# Sheet6.net
KiCad netlist of a schematic drawn in Altium Designer
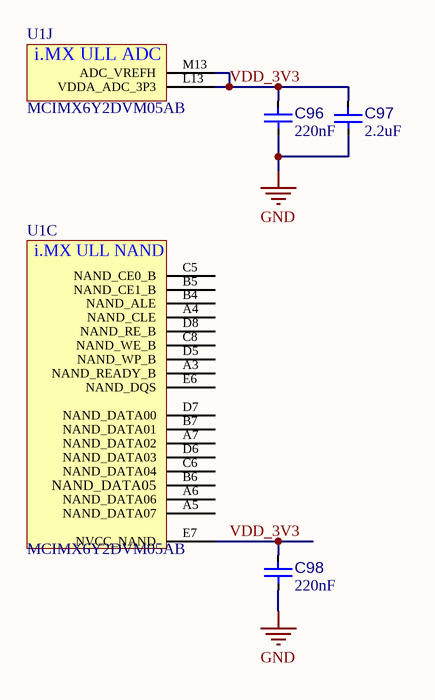
[diagram p0: Sheet6.SchDoc]

(export (version "E")
  (design (tool "Eeschema 10.0.6"))
  (components
    (comp (ref "C96")
      (value "220nF")
      (footprint "0402-SMD-CAP")
      (fields
        (field (name "TOLERANCE") "10%")
        (field (name "VOLTAGE") "16V")
        (field (name "Comment") "GRM155R71C224KA12D")
      )
      (libsource (lib "Budapest University of Technology and Economics") (part "CAP-NP-2"))
    )
    (comp (ref "C97")
      (value "2.2uF")
      (footprint "0603-SMD-CAP")
      (description "CAP CER 2.2UF 10V X7R 0603")
      (fields (field (name "VOLTAGE") "10V") (field (name "TOLERANCE") "10%"))
      (libsource (lib "Budapest University of Technology and Economics") (part "CAP-NP-2"))
    )
    (comp (ref "C98")
      (value "220nF")
      (footprint "0402-SMD-CAP")
      (fields
        (field (name "TOLERANCE") "10%")
        (field (name "VOLTAGE") "16V")
        (field (name "Comment") "GRM155R71C224KA12D")
      )
      (libsource (lib "Budapest University of Technology and Economics") (part "CAP-NP-2"))
    )
    (comp (ref "U1")
      (value "MCIMX6Y2DVM05AB")
      (footprint "BGA100P9X9-81A")
      (libsource (lib "Budapest University of Technology and Economics") (part "MCIMX6Y2DVM05AB"))
    )
  )
  (nets
    (net (code "1") (name "/VDD_3V3") (class "Default")
      (node (ref "C96") (pin "1") (pinfunction "1_1") (pintype "passive"))
      (node (ref "C97") (pin "2") (pinfunction "2_2") (pintype "passive"))
      (node (ref "C98") (pin "1") (pinfunction "1_1") (pintype "passive"))
      (node (ref "U1") (pin "E7") (pinfunction "NVCC_NAND_E7") (pintype "passive"))
      (node (ref "U1") (pin "L13") (pinfunction "VDDA_ADC_3P3_L13") (pintype "passive"))
      (node (ref "U1") (pin "M13") (pinfunction "ADC_VREFH_M13") (pintype "passive"))
    )
    (net (code "2") (name "GND") (class "Default")
      (node (ref "C96") (pin "2") (pinfunction "2_2") (pintype "passive"))
      (node (ref "C97") (pin "1") (pinfunction "1_1") (pintype "passive"))
      (node (ref "C98") (pin "2") (pinfunction "2_2") (pintype "passive"))
    )
    (net (code "3") (name "unconnected-(U1C-NAND_ALE-PadB4)") (class "Default")
      (node (ref "U1") (pin "B4") (pinfunction "NAND_ALE_B4") (pintype "passive"))
    )
    (net (code "4") (name "unconnected-(U1C-NAND_CE0_B-PadC5)") (class "Default")
      (node (ref "U1") (pin "C5") (pinfunction "NAND_CE0_B_C5") (pintype "passive"))
    )
    (net (code "5") (name "unconnected-(U1C-NAND_CE1_B-PadB5)") (class "Default")
      (node (ref "U1") (pin "B5") (pinfunction "NAND_CE1_B_B5") (pintype "passive"))
    )
    (net (code "6") (name "unconnected-(U1C-NAND_CLE-PadA4)") (class "Default")
      (node (ref "U1") (pin "A4") (pinfunction "NAND_CLE_A4") (pintype "passive"))
    )
    (net (code "7") (name "unconnected-(U1C-NAND_DATA00-PadD7)") (class "Default")
      (node (ref "U1") (pin "D7") (pinfunction "NAND_DATA00_D7") (pintype "passive"))
    )
    (net (code "8") (name "unconnected-(U1C-NAND_DATA01-PadB7)") (class "Default")
      (node (ref "U1") (pin "B7") (pinfunction "NAND_DATA01_B7") (pintype "passive"))
    )
    (net (code "9") (name "unconnected-(U1C-NAND_DATA02-PadA7)") (class "Default")
      (node (ref "U1") (pin "A7") (pinfunction "NAND_DATA02_A7") (pintype "passive"))
    )
    (net (code "10") (name "unconnected-(U1C-NAND_DATA03-PadD6)") (class "Default")
      (node (ref "U1") (pin "D6") (pinfunction "NAND_DATA03_D6") (pintype "passive"))
    )
    (net (code "11") (name "unconnected-(U1C-NAND_DATA04-PadC6)") (class "Default")
      (node (ref "U1") (pin "C6") (pinfunction "NAND_DATA04_C6") (pintype "passive"))
    )
    (net (code "12") (name "unconnected-(U1C-NAND_DATA05-PadB6)") (class "Default")
      (node (ref "U1") (pin "B6") (pinfunction "NAND_DATA05_B6") (pintype "passive"))
    )
    (net (code "13") (name "unconnected-(U1C-NAND_DATA06-PadA6)") (class "Default")
      (node (ref "U1") (pin "A6") (pinfunction "NAND_DATA06_A6") (pintype "passive"))
    )
    (net (code "14") (name "unconnected-(U1C-NAND_DATA07-PadA5)") (class "Default")
      (node (ref "U1") (pin "A5") (pinfunction "NAND_DATA07_A5") (pintype "passive"))
    )
    (net (code "15") (name "unconnected-(U1C-NAND_DQS-PadE6)") (class "Default")
      (node (ref "U1") (pin "E6") (pinfunction "NAND_DQS_E6") (pintype "passive"))
    )
    (net (code "16") (name "unconnected-(U1C-NAND_READY_B-PadA3)") (class "Default")
      (node (ref "U1") (pin "A3") (pinfunction "NAND_READY_B_A3") (pintype "passive"))
    )
    (net (code "17") (name "unconnected-(U1C-NAND_RE_B-PadD8)") (class "Default")
      (node (ref "U1") (pin "D8") (pinfunction "NAND_RE_B_D8") (pintype "passive"))
    )
    (net (code "18") (name "unconnected-(U1C-NAND_WE_B-PadC8)") (class "Default")
      (node (ref "U1") (pin "C8") (pinfunction "NAND_WE_B_C8") (pintype "passive"))
    )
    (net (code "19") (name "unconnected-(U1C-NAND_WP_B-PadD5)") (class "Default")
      (node (ref "U1") (pin "D5") (pinfunction "NAND_WP_B_D5") (pintype "passive"))
    )
  )
)
